# Polysex_board.net
KiCad netlist of a schematic drawn in EAGLE
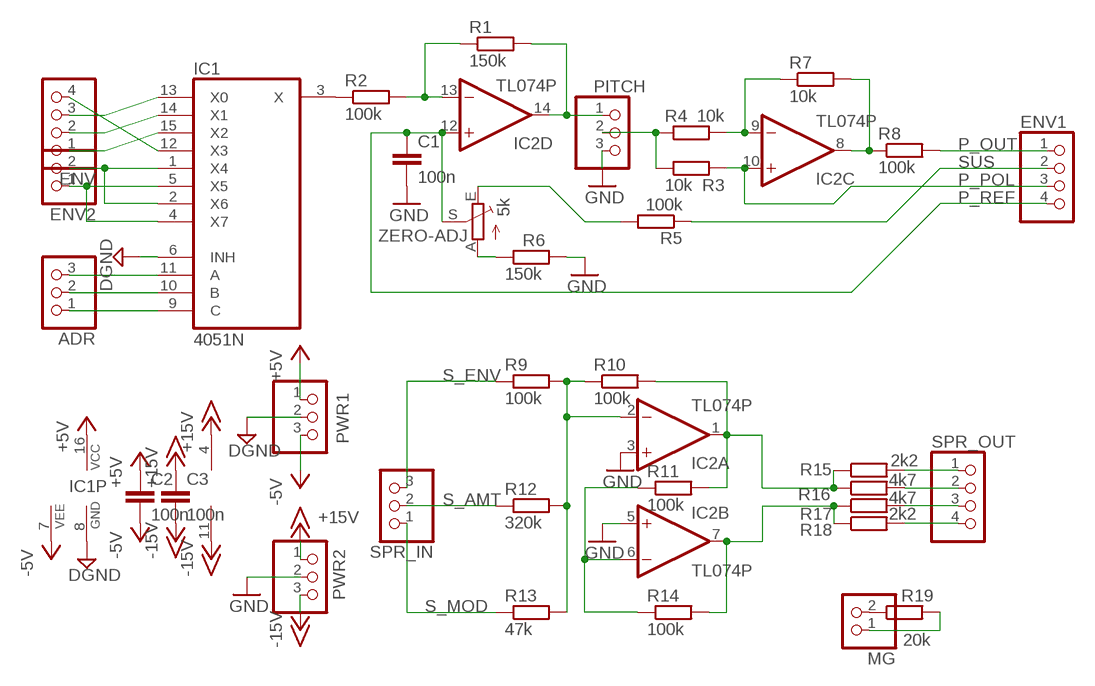
[diagram p0: schematic, sheet 1]

(export (version "E")
  (design (tool "Eeschema 10.0.6"))
  (components
    (comp (ref "ADR")
      (value "PINHD-1X3")
      (footprint "eagle-import:1X03")
      (libsource (lib "eagle-import") (part "PINHD-1X3"))
    )
    (comp (ref "C1")
      (value "100n")
      (footprint "eagle-import:C025-025X050")
      (libsource (lib "eagle-import") (part "C-EU025-025X050"))
    )
    (comp (ref "C2")
      (value "100n")
      (footprint "eagle-import:C025-025X050")
      (libsource (lib "eagle-import") (part "C-EU025-025X050"))
    )
    (comp (ref "C3")
      (value "100n")
      (footprint "eagle-import:C025-025X050")
      (libsource (lib "eagle-import") (part "C-EU025-025X050"))
    )
    (comp (ref "ENV")
      (value "PINHD-1X4")
      (footprint "eagle-import:1X04")
      (libsource (lib "eagle-import") (part "PINHD-1X4"))
    )
    (comp (ref "ENV1")
      (value "PINHD-1X4")
      (footprint "eagle-import:1X04")
      (libsource (lib "eagle-import") (part "PINHD-1X4"))
    )
    (comp (ref "ENV2")
      (value "PINHD-1X2")
      (footprint "eagle-import:1X02")
      (libsource (lib "eagle-import") (part "PINHD-1X2"))
    )
    (comp (ref "IC1")
      (value "4051N")
      (footprint "eagle-import:DIL16")
      (libsource (lib "eagle-import") (part "4051N"))
    )
    (comp (ref "IC2")
      (value "TL074P")
      (footprint "eagle-import:DIL14")
      (libsource (lib "eagle-import") (part "TL074P"))
    )
    (comp (ref "MG")
      (value "PINHD-1X2")
      (footprint "eagle-import:1X02")
      (libsource (lib "eagle-import") (part "PINHD-1X2"))
    )
    (comp (ref "PITCH")
      (value "PINHD-1X3")
      (footprint "eagle-import:1X03")
      (libsource (lib "eagle-import") (part "PINHD-1X3"))
    )
    (comp (ref "PWR1")
      (value "PINHD-1X3")
      (footprint "eagle-import:1X03")
      (libsource (lib "eagle-import") (part "PINHD-1X3"))
    )
    (comp (ref "PWR2")
      (value "PINHD-1X3")
      (footprint "eagle-import:1X03")
      (libsource (lib "eagle-import") (part "PINHD-1X3"))
    )
    (comp (ref "R1")
      (value "150k")
      (footprint "eagle-import:0204_7")
      (libsource (lib "eagle-import") (part "R-EU_0204/7"))
    )
    (comp (ref "R2")
      (value "100k")
      (footprint "eagle-import:0204_7")
      (libsource (lib "eagle-import") (part "R-EU_0204/7"))
    )
    (comp (ref "R3")
      (value "10k")
      (footprint "eagle-import:0204_7")
      (libsource (lib "eagle-import") (part "R-EU_0204/7"))
    )
    (comp (ref "R4")
      (value "10k")
      (footprint "eagle-import:0204_7")
      (libsource (lib "eagle-import") (part "R-EU_0204/7"))
    )
    (comp (ref "R5")
      (value "100k")
      (footprint "eagle-import:0204_7")
      (libsource (lib "eagle-import") (part "R-EU_0204/7"))
    )
    (comp (ref "R6")
      (value "150k")
      (footprint "eagle-import:0204_7")
      (libsource (lib "eagle-import") (part "R-EU_0204/7"))
    )
    (comp (ref "R7")
      (value "10k")
      (footprint "eagle-import:0204_7")
      (libsource (lib "eagle-import") (part "R-EU_0204/7"))
    )
    (comp (ref "R8")
      (value "100k")
      (footprint "eagle-import:0204_7")
      (libsource (lib "eagle-import") (part "R-EU_0204/7"))
    )
    (comp (ref "R9")
      (value "100k")
      (footprint "eagle-import:0204_7")
      (libsource (lib "eagle-import") (part "R-EU_0204/7"))
    )
    (comp (ref "R10")
      (value "100k")
      (footprint "eagle-import:0204_7")
      (libsource (lib "eagle-import") (part "R-EU_0204/7"))
    )
    (comp (ref "R11")
      (value "100k")
      (footprint "eagle-import:0204_7")
      (libsource (lib "eagle-import") (part "R-EU_0204/7"))
    )
    (comp (ref "R12")
      (value "320k")
      (footprint "eagle-import:0204_7")
      (libsource (lib "eagle-import") (part "R-EU_0204/7"))
    )
    (comp (ref "R13")
      (value "47k")
      (footprint "eagle-import:0204_7")
      (libsource (lib "eagle-import") (part "R-EU_0204/7"))
    )
    (comp (ref "R14")
      (value "100k")
      (footprint "eagle-import:0204_7")
      (libsource (lib "eagle-import") (part "R-EU_0204/7"))
    )
    (comp (ref "R15")
      (value "2k2")
      (footprint "eagle-import:0204_7")
      (libsource (lib "eagle-import") (part "R-EU_0204/7"))
    )
    (comp (ref "R16")
      (value "4k7")
      (footprint "eagle-import:0204_7")
      (libsource (lib "eagle-import") (part "R-EU_0204/7"))
    )
    (comp (ref "R17")
      (value "4k7")
      (footprint "eagle-import:0204_7")
      (libsource (lib "eagle-import") (part "R-EU_0204/7"))
    )
    (comp (ref "R18")
      (value "2k2")
      (footprint "eagle-import:0204_7")
      (libsource (lib "eagle-import") (part "R-EU_0204/7"))
    )
    (comp (ref "R19")
      (value "20k")
      (footprint "eagle-import:0204_7")
      (libsource (lib "eagle-import") (part "R-EU_0204/7"))
    )
    (comp (ref "SPR_IN")
      (value "PINHD-1X3")
      (footprint "eagle-import:1X03")
      (libsource (lib "eagle-import") (part "PINHD-1X3"))
    )
    (comp (ref "SPR_OUT")
      (value "PINHD-1X4")
      (footprint "eagle-import:1X04")
      (libsource (lib "eagle-import") (part "PINHD-1X4"))
    )
    (comp (ref "ZERO-ADJ")
      (value "5k")
      (footprint "eagle-import:CA6V")
      (libsource (lib "eagle-import") (part "TRIM_EU-CA6V"))
    )
  )
  (nets
    (net (code "1") (name "+5V") (class "Default")
      (node (ref "C2") (pin "1") (pinfunction "1_1") (pintype "passive"))
      (node (ref "IC1") (pin "16") (pinfunction "VCC_16") (pintype "power_in"))
      (node (ref "PWR1") (pin "1") (pinfunction "1_1") (pintype "passive"))
    )
    (net (code "2") (name "+15V") (class "Default")
      (node (ref "C3") (pin "1") (pinfunction "1_1") (pintype "passive"))
      (node (ref "IC2") (pin "4") (pinfunction "V+_4") (pintype "power_in"))
      (node (ref "PWR2") (pin "1") (pinfunction "1_1") (pintype "passive"))
    )
    (net (code "3") (name "-5V") (class "Default")
      (node (ref "C2") (pin "2") (pinfunction "2_2") (pintype "passive"))
      (node (ref "IC1") (pin "7") (pinfunction "VEE_7") (pintype "power_in"))
      (node (ref "PWR1") (pin "3") (pinfunction "3_3") (pintype "passive"))
    )
    (net (code "4") (name "-15V") (class "Default")
      (node (ref "C3") (pin "2") (pinfunction "2_2") (pintype "passive"))
      (node (ref "IC2") (pin "11") (pinfunction "V-_11") (pintype "power_in"))
      (node (ref "PWR2") (pin "3") (pinfunction "3_3") (pintype "passive"))
    )
    (net (code "5") (name "/P_OUT") (class "Default")
      (node (ref "ENV1") (pin "1") (pinfunction "1_1") (pintype "passive"))
      (node (ref "R8") (pin "2") (pinfunction "2_2") (pintype "passive"))
    )
    (net (code "6") (name "/P_POL") (class "Default")
      (node (ref "ENV1") (pin "3") (pinfunction "3_3") (pintype "passive"))
      (node (ref "IC2") (pin "10") (pinfunction "+IN_10") (pintype "input"))
      (node (ref "R3") (pin "2") (pinfunction "2_2") (pintype "passive"))
    )
    (net (code "7") (name "/P_REF") (class "Default")
      (node (ref "C1") (pin "1") (pinfunction "1_1") (pintype "passive"))
      (node (ref "ENV1") (pin "4") (pinfunction "4_4") (pintype "passive"))
      (node (ref "IC2") (pin "12") (pinfunction "+IN_12") (pintype "input"))
      (node (ref "ZERO-ADJ") (pin "S") (pinfunction "S_S") (pintype "passive"))
    )
    (net (code "8") (name "/SUS") (class "Default")
      (node (ref "ENV1") (pin "2") (pinfunction "2_2") (pintype "passive"))
      (node (ref "R5") (pin "1") (pinfunction "1_1") (pintype "passive"))
    )
    (net (code "9") (name "/S_AMT") (class "Default")
      (node (ref "R12") (pin "1") (pinfunction "1_1") (pintype "passive"))
      (node (ref "SPR_IN") (pin "2") (pinfunction "2_2") (pintype "passive"))
    )
    (net (code "10") (name "/S_ENV") (class "Default")
      (node (ref "R9") (pin "1") (pinfunction "1_1") (pintype "passive"))
      (node (ref "SPR_IN") (pin "3") (pinfunction "3_3") (pintype "passive"))
    )
    (net (code "11") (name "/S_MOD") (class "Default")
      (node (ref "R13") (pin "1") (pinfunction "1_1") (pintype "passive"))
      (node (ref "SPR_IN") (pin "1") (pinfunction "1_1") (pintype "passive"))
    )
    (net (code "12") (name "DGND") (class "Default")
      (node (ref "IC1") (pin "6") (pinfunction "INH_6") (pintype "input"))
      (node (ref "IC1") (pin "8") (pinfunction "GND_8") (pintype "power_in"))
      (node (ref "PWR1") (pin "2") (pinfunction "2_2") (pintype "passive"))
    )
    (net (code "13") (name "GND") (class "Default")
      (node (ref "C1") (pin "2") (pinfunction "2_2") (pintype "passive"))
      (node (ref "IC2") (pin "3") (pinfunction "+IN_3") (pintype "input"))
      (node (ref "IC2") (pin "5") (pinfunction "+IN_5") (pintype "input"))
      (node (ref "PITCH") (pin "3") (pinfunction "3_3") (pintype "passive"))
      (node (ref "PWR2") (pin "2") (pinfunction "2_2") (pintype "passive"))
      (node (ref "R6") (pin "2") (pinfunction "2_2") (pintype "passive"))
    )
    (net (code "14") (name "Net-(IC1A-A)") (class "Default")
      (node (ref "ADR") (pin "3") (pinfunction "3_3") (pintype "passive"))
      (node (ref "IC1") (pin "11") (pinfunction "A_11") (pintype "input"))
    )
    (net (code "15") (name "Net-(IC1A-B)") (class "Default")
      (node (ref "ADR") (pin "2") (pinfunction "2_2") (pintype "passive"))
      (node (ref "IC1") (pin "10") (pinfunction "B_10") (pintype "input"))
    )
    (net (code "16") (name "Net-(IC1A-C)") (class "Default")
      (node (ref "ADR") (pin "1") (pinfunction "1_1") (pintype "passive"))
      (node (ref "IC1") (pin "9") (pinfunction "C_9") (pintype "input"))
    )
    (net (code "17") (name "Net-(IC1A-X)") (class "Default")
      (node (ref "IC1") (pin "3") (pinfunction "X_3") (pintype "bidirectional"))
      (node (ref "R2") (pin "1") (pinfunction "1_1") (pintype "passive"))
    )
    (net (code "18") (name "Net-(IC1A-X0)") (class "Default")
      (node (ref "ENV") (pin "3") (pinfunction "3_3") (pintype "passive"))
      (node (ref "IC1") (pin "13") (pinfunction "X0_13") (pintype "bidirectional"))
    )
    (net (code "19") (name "Net-(IC1A-X1)") (class "Default")
      (node (ref "ENV") (pin "2") (pinfunction "2_2") (pintype "passive"))
      (node (ref "IC1") (pin "14") (pinfunction "X1_14") (pintype "bidirectional"))
    )
    (net (code "20") (name "Net-(IC1A-X2)") (class "Default")
      (node (ref "ENV") (pin "1") (pinfunction "1_1") (pintype "passive"))
      (node (ref "IC1") (pin "15") (pinfunction "X2_15") (pintype "bidirectional"))
    )
    (net (code "21") (name "Net-(IC1A-X3)") (class "Default")
      (node (ref "ENV") (pin "4") (pinfunction "4_4") (pintype "passive"))
      (node (ref "IC1") (pin "12") (pinfunction "X3_12") (pintype "bidirectional"))
    )
    (net (code "22") (name "Net-(IC1A-X4)") (class "Default")
      (node (ref "ENV2") (pin "2") (pinfunction "2_2") (pintype "passive"))
      (node (ref "IC1") (pin "1") (pinfunction "X4_1") (pintype "bidirectional"))
      (node (ref "IC1") (pin "2") (pinfunction "X6_2") (pintype "bidirectional"))
    )
    (net (code "23") (name "Net-(IC1A-X5)") (class "Default")
      (node (ref "ENV2") (pin "1") (pinfunction "1_1") (pintype "passive"))
      (node (ref "IC1") (pin "4") (pinfunction "X7_4") (pintype "bidirectional"))
      (node (ref "IC1") (pin "5") (pinfunction "X5_5") (pintype "bidirectional"))
    )
    (net (code "24") (name "Net-(IC2A--IN)") (class "Default")
      (node (ref "IC2") (pin "2") (pinfunction "-IN_2") (pintype "input"))
      (node (ref "R10") (pin "1") (pinfunction "1_1") (pintype "passive"))
      (node (ref "R12") (pin "2") (pinfunction "2_2") (pintype "passive"))
      (node (ref "R13") (pin "2") (pinfunction "2_2") (pintype "passive"))
      (node (ref "R9") (pin "2") (pinfunction "2_2") (pintype "passive"))
    )
    (net (code "25") (name "Net-(IC2A-OUT)") (class "Default")
      (node (ref "IC2") (pin "1") (pinfunction "OUT_1") (pintype "output"))
      (node (ref "R10") (pin "2") (pinfunction "2_2") (pintype "passive"))
      (node (ref "R11") (pin "2") (pinfunction "2_2") (pintype "passive"))
      (node (ref "R15") (pin "1") (pinfunction "1_1") (pintype "passive"))
      (node (ref "R16") (pin "1") (pinfunction "1_1") (pintype "passive"))
    )
    (net (code "26") (name "Net-(IC2B--IN)") (class "Default")
      (node (ref "IC2") (pin "6") (pinfunction "-IN_6") (pintype "input"))
      (node (ref "R11") (pin "1") (pinfunction "1_1") (pintype "passive"))
      (node (ref "R14") (pin "1") (pinfunction "1_1") (pintype "passive"))
    )
    (net (code "27") (name "Net-(IC2B-OUT)") (class "Default")
      (node (ref "IC2") (pin "7") (pinfunction "OUT_7") (pintype "output"))
      (node (ref "R14") (pin "2") (pinfunction "2_2") (pintype "passive"))
      (node (ref "R17") (pin "1") (pinfunction "1_1") (pintype "passive"))
      (node (ref "R18") (pin "1") (pinfunction "1_1") (pintype "passive"))
    )
    (net (code "28") (name "Net-(IC2C--IN)") (class "Default")
      (node (ref "IC2") (pin "9") (pinfunction "-IN_9") (pintype "input"))
      (node (ref "R4") (pin "2") (pinfunction "2_2") (pintype "passive"))
      (node (ref "R7") (pin "1") (pinfunction "1_1") (pintype "passive"))
    )
    (net (code "29") (name "Net-(IC2C-OUT)") (class "Default")
      (node (ref "IC2") (pin "8") (pinfunction "OUT_8") (pintype "output"))
      (node (ref "R7") (pin "2") (pinfunction "2_2") (pintype "passive"))
      (node (ref "R8") (pin "1") (pinfunction "1_1") (pintype "passive"))
    )
    (net (code "30") (name "Net-(IC2D--IN)") (class "Default")
      (node (ref "IC2") (pin "13") (pinfunction "-IN_13") (pintype "input"))
      (node (ref "R1") (pin "1") (pinfunction "1_1") (pintype "passive"))
      (node (ref "R2") (pin "2") (pinfunction "2_2") (pintype "passive"))
    )
    (net (code "31") (name "Net-(IC2D-OUT)") (class "Default")
      (node (ref "IC2") (pin "14") (pinfunction "OUT_14") (pintype "output"))
      (node (ref "PITCH") (pin "1") (pinfunction "1_1") (pintype "passive"))
      (node (ref "R1") (pin "2") (pinfunction "2_2") (pintype "passive"))
    )
    (net (code "32") (name "Net-(MG-Pad1)") (class "Default")
      (node (ref "MG") (pin "1") (pinfunction "1_1") (pintype "passive"))
      (node (ref "R19") (pin "2") (pinfunction "2_2") (pintype "passive"))
    )
    (net (code "33") (name "Net-(MG-Pad2)") (class "Default")
      (node (ref "MG") (pin "2") (pinfunction "2_2") (pintype "passive"))
      (node (ref "R19") (pin "1") (pinfunction "1_1") (pintype "passive"))
    )
    (net (code "34") (name "Net-(PITCH-Pad2)") (class "Default")
      (node (ref "PITCH") (pin "2") (pinfunction "2_2") (pintype "passive"))
      (node (ref "R3") (pin "1") (pinfunction "1_1") (pintype "passive"))
      (node (ref "R4") (pin "1") (pinfunction "1_1") (pintype "passive"))
    )
    (net (code "35") (name "Net-(R5-Pad2)") (class "Default")
      (node (ref "R5") (pin "2") (pinfunction "2_2") (pintype "passive"))
      (node (ref "ZERO-ADJ") (pin "E") (pinfunction "E_E") (pintype "passive"))
    )
    (net (code "36") (name "Net-(R6-Pad1)") (class "Default")
      (node (ref "R6") (pin "1") (pinfunction "1_1") (pintype "passive"))
      (node (ref "ZERO-ADJ") (pin "A") (pinfunction "A_A") (pintype "passive"))
    )
    (net (code "37") (name "Net-(R15-Pad2)") (class "Default")
      (node (ref "R15") (pin "2") (pinfunction "2_2") (pintype "passive"))
      (node (ref "SPR_OUT") (pin "1") (pinfunction "1_1") (pintype "passive"))
    )
    (net (code "38") (name "Net-(R16-Pad2)") (class "Default")
      (node (ref "R16") (pin "2") (pinfunction "2_2") (pintype "passive"))
      (node (ref "SPR_OUT") (pin "2") (pinfunction "2_2") (pintype "passive"))
    )
    (net (code "39") (name "Net-(R17-Pad2)") (class "Default")
      (node (ref "R17") (pin "2") (pinfunction "2_2") (pintype "passive"))
      (node (ref "SPR_OUT") (pin "3") (pinfunction "3_3") (pintype "passive"))
    )
    (net (code "40") (name "Net-(R18-Pad2)") (class "Default")
      (node (ref "R18") (pin "2") (pinfunction "2_2") (pintype "passive"))
      (node (ref "SPR_OUT") (pin "4") (pinfunction "4_4") (pintype "passive"))
    )
  )
)
